# Sheet1.net
KiCad netlist of a schematic drawn in Altium Designer
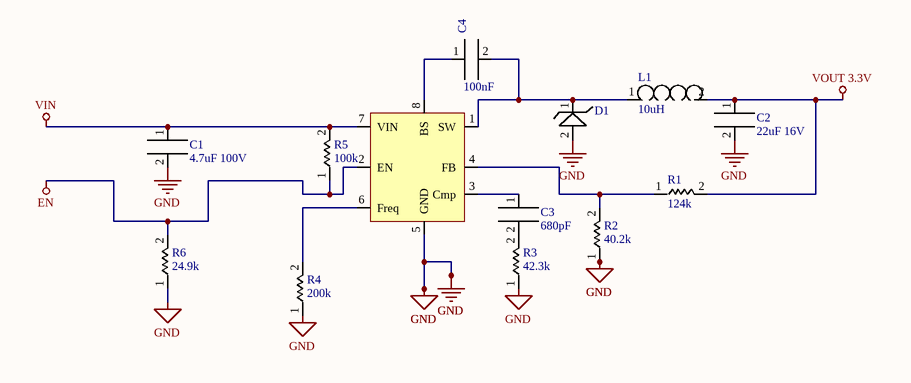
[diagram p0: Sheet1.SchDoc]

(export (version "E")
  (design (tool "Eeschema 10.0.6"))
  (components
    (comp (ref "C1")
      (value "4.7uF 100V")
      (footprint "CAPC1005X06N")
      (libsource (lib "capac") (part "Component_1"))
    )
    (comp (ref "C2")
      (value "22uF 16V")
      (footprint "CAPC1005X06N")
      (libsource (lib "capac") (part "Component_1"))
    )
    (comp (ref "C3")
      (value "680pF")
      (footprint "CAPC1005X06N")
      (libsource (lib "capac") (part "Component_1"))
    )
    (comp (ref "C4")
      (value "100nF")
      (footprint "CAPC1005X06N")
      (libsource (lib "capac") (part "Component_1"))
    )
    (comp (ref "D1")
      (value "Schottky")
      (footprint "sss")
      (libsource (lib "Schottky_diode") (part "Schottky"))
    )
    (comp (ref "L1")
      (value "10uH")
      (footprint "INDUCTOR")
      (description "4.7 µH Shielded Drum Core, Wirewound Inductor 2.9 A 35mOhm Max Nonstandard")
      (libsource (lib "inductor") (part "Inducor"))
    )
    (comp (ref "MP4560DN**")
      (value "Component_1")
      (footprint "SOIC127P600X170_HS-9N")
      (description "MP4560\r\n2A, 2MHz, 55V\r\nStep-Down Converter")
      (fields
        (field (name "MANUFACTURER") "Monolothic Power")
        (field (name "MANUFACTURER PART NO") "MP4560DN**")
      )
      (libsource (lib "MP4560") (part "Component_1"))
    )
    (comp (ref "R1")
      (value "124k")
      (footprint "DIOMELF3516N")
      (libsource (lib "resistor_100k") (part "Component_1"))
    )
    (comp (ref "R2")
      (value "40.2k")
      (footprint "DIOMELF3516N")
      (libsource (lib "resistor_100k") (part "Component_1"))
    )
    (comp (ref "R3")
      (value "42.3k")
      (footprint "DIOMELF3516N")
      (libsource (lib "resistor_100k") (part "Component_1"))
    )
    (comp (ref "R4")
      (value "200k")
      (footprint "DIOMELF3516N")
      (libsource (lib "resistor_100k") (part "Component_1"))
    )
    (comp (ref "R5") (value "100k") (footprint "DIOMELF3516N") (libsource (lib "") (part "Component_1_1")))
    (comp (ref "R6")
      (value "24.9k")
      (footprint "DIOMELF3516N")
      (libsource (lib "resistor_100k") (part "Component_1"))
    )
  )
  (nets
    (net (code "1") (name "EN") (class "Default")
      (node (ref "MP4560DN**") (pin "2") (pinfunction "EN_2") (pintype "passive"))
      (node (ref "R5") (pin "1") (pintype "passive"))
      (node (ref "R6") (pin "2") (pintype "passive"))
    )
    (net (code "2") (name "GND") (class "Default")
      (node (ref "C1") (pin "2") (pintype "passive"))
      (node (ref "C2") (pin "2") (pintype "passive"))
      (node (ref "D1") (pin "2") (pintype "passive"))
      (node (ref "MP4560DN**") (pin "5") (pinfunction "GND_5") (pintype "passive"))
      (node (ref "R2") (pin "1") (pintype "passive"))
      (node (ref "R3") (pin "1") (pintype "passive"))
      (node (ref "R4") (pin "1") (pintype "passive"))
      (node (ref "R6") (pin "1") (pintype "passive"))
    )
    (net (code "3") (name "Net-(C3-C7)") (class "Default")
      (node (ref "C3") (pin "1") (pinfunction "C7_1") (pintype "passive"))
      (node (ref "MP4560DN**") (pin "3") (pinfunction "Cmp_3") (pintype "passive"))
    )
    (net (code "4") (name "Net-(C3-Pad2)") (class "Default")
      (node (ref "C3") (pin "2") (pintype "passive"))
      (node (ref "R3") (pin "2") (pintype "passive"))
    )
    (net (code "5") (name "Net-(C4-C7)") (class "Default")
      (node (ref "C4") (pin "1") (pinfunction "C7_1") (pintype "passive"))
      (node (ref "MP4560DN**") (pin "8") (pinfunction "BS_8") (pintype "passive"))
    )
    (net (code "6") (name "Net-(MP4560DN**-FB)") (class "Default")
      (node (ref "MP4560DN**") (pin "4") (pinfunction "FB_4") (pintype "passive"))
      (node (ref "R1") (pin "1") (pintype "passive"))
      (node (ref "R2") (pin "2") (pintype "passive"))
    )
    (net (code "7") (name "Net-(MP4560DN**-Freq)") (class "Default")
      (node (ref "MP4560DN**") (pin "6") (pinfunction "Freq_6") (pintype "passive"))
      (node (ref "R4") (pin "2") (pintype "passive"))
    )
    (net (code "8") (name "Net-(MP4560DN**-SW)") (class "Default")
      (node (ref "C4") (pin "2") (pintype "passive"))
      (node (ref "D1") (pin "1") (pintype "passive"))
      (node (ref "L1") (pin "1") (pintype "passive"))
      (node (ref "MP4560DN**") (pin "1") (pinfunction "SW_1") (pintype "passive"))
    )
    (net (code "9") (name "VIN") (class "Default")
      (node (ref "C1") (pin "1") (pinfunction "C7_1") (pintype "passive"))
      (node (ref "MP4560DN**") (pin "7") (pinfunction "VIN_7") (pintype "passive"))
      (node (ref "R5") (pin "2") (pintype "passive"))
    )
    (net (code "10") (name "VOUT 3.3V") (class "Default")
      (node (ref "C2") (pin "1") (pinfunction "C7_1") (pintype "passive"))
      (node (ref "L1") (pin "2") (pintype "passive"))
      (node (ref "R1") (pin "2") (pintype "passive"))
    )
  )
)
